# minimumSystem_Hafidin_Alfath.net
KiCad netlist of a schematic drawn in EAGLE
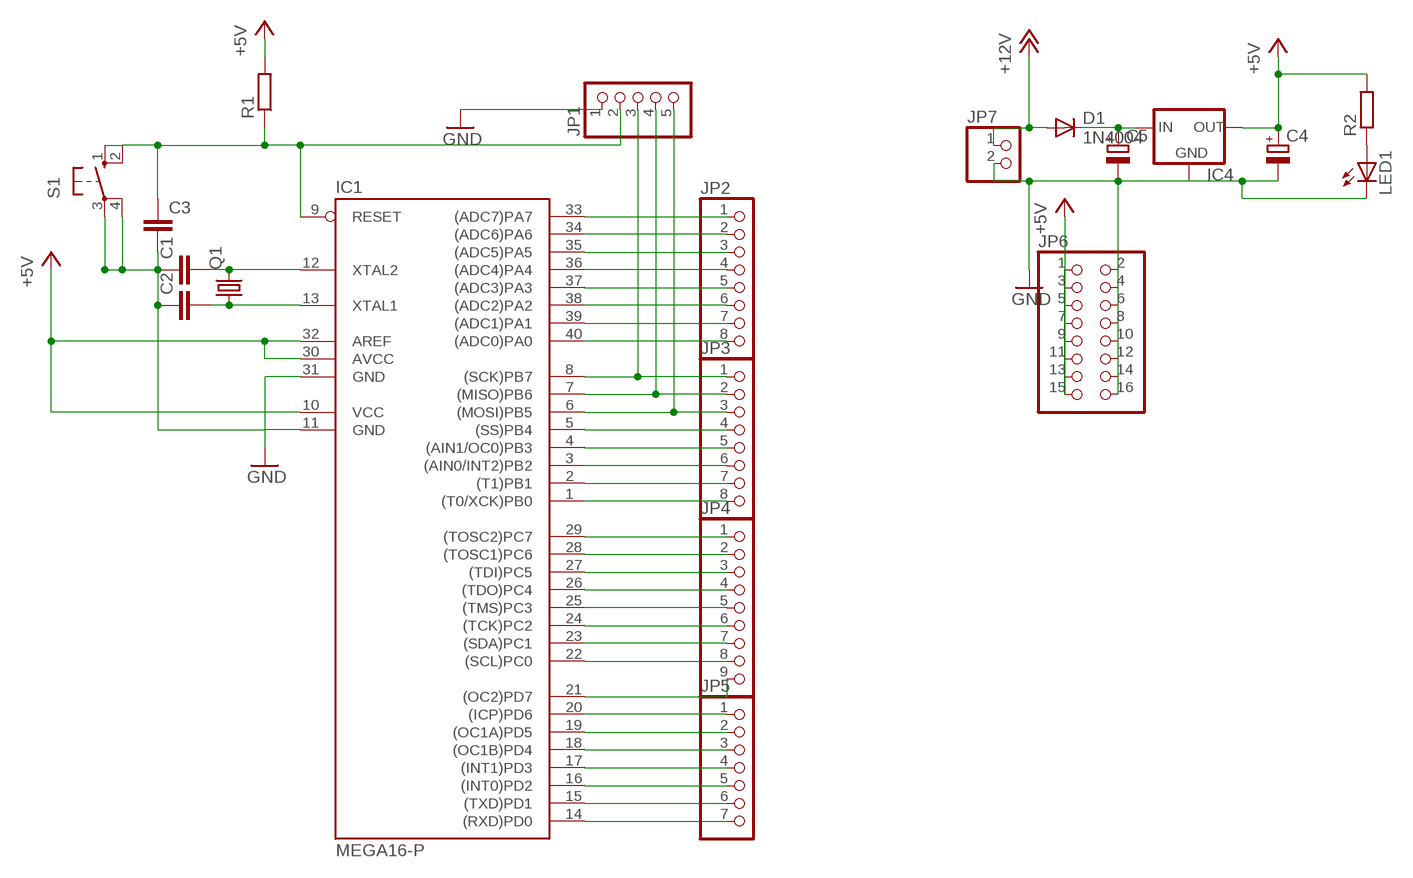
[diagram p0: schematic, sheet 1]

(export (version "E")
  (design (tool "Eeschema 10.0.6"))
  (components
    (comp (ref "C1")
      (value "C-EU025-024X044")
      (footprint "eagle-import:C025-024X044")
      (libsource (lib "eagle-import") (part "C-EU025-024X044"))
    )
    (comp (ref "C2")
      (value "C-EU025-024X044")
      (footprint "eagle-import:C025-024X044")
      (libsource (lib "eagle-import") (part "C-EU025-024X044"))
    )
    (comp (ref "C3")
      (value "C-EU050-025X075")
      (footprint "eagle-import:C050-025X075")
      (libsource (lib "eagle-import") (part "resistor_C-EU050-025X075"))
    )
    (comp (ref "C4")
      (value "CPOL-EUE2.5-5")
      (footprint "eagle-import:E2,5-5")
      (libsource (lib "eagle-import") (part "CPOL-EUE2.5-5"))
    )
    (comp (ref "C5")
      (value "CPOL-EUE2.5-5")
      (footprint "eagle-import:E2,5-5")
      (libsource (lib "eagle-import") (part "CPOL-EUE2.5-5"))
    )
    (comp (ref "D1")
      (value "1N4004")
      (footprint "eagle-import:DO41-10")
      (libsource (lib "eagle-import") (part "1N4004"))
    )
    (comp (ref "IC1")
      (value "MEGA16-P")
      (footprint "eagle-import:DIL40")
      (fields (field (name "MPN") "ATMEGA16-16PU"))
      (libsource (lib "eagle-import") (part "MEGA16-P"))
    )
    (comp (ref "IC4")
      (value "78XXS")
      (footprint "eagle-import:78XXS")
      (libsource (lib "eagle-import") (part "78XXS"))
    )
    (comp (ref "JP1")
      (value "PINHD-1X5")
      (footprint "eagle-import:1X05")
      (libsource (lib "eagle-import") (part "PINHD-1X5"))
    )
    (comp (ref "JP2")
      (value "PINHD-1X8")
      (footprint "eagle-import:1X08")
      (libsource (lib "eagle-import") (part "PINHD-1X8"))
    )
    (comp (ref "JP3")
      (value "PINHD-1X8")
      (footprint "eagle-import:1X08")
      (libsource (lib "eagle-import") (part "PINHD-1X8"))
    )
    (comp (ref "JP4")
      (value "PINHD-1X9")
      (footprint "eagle-import:1X09")
      (libsource (lib "eagle-import") (part "PINHD-1X9"))
    )
    (comp (ref "JP5")
      (value "PINHD-1X7")
      (footprint "eagle-import:1X07")
      (libsource (lib "eagle-import") (part "PINHD-1X7"))
    )
    (comp (ref "JP6")
      (value "PINHD-2X8")
      (footprint "eagle-import:2X08")
      (libsource (lib "eagle-import") (part "PINHD-2X8"))
    )
    (comp (ref "JP7")
      (value "PINHD-1X2")
      (footprint "eagle-import:1X02")
      (libsource (lib "eagle-import") (part "PINHD-1X2"))
    )
    (comp (ref "LED1")
      (value "LED5MM")
      (footprint "eagle-import:LED5MM")
      (libsource (lib "eagle-import") (part "LED5MM"))
    )
    (comp (ref "Q1")
      (value "CRYSTALHC49U-V")
      (footprint "eagle-import:HC49U-V")
      (libsource (lib "eagle-import") (part "CRYSTALHC49U-V"))
    )
    (comp (ref "R1")
      (value "R-EU_0204/7")
      (footprint "eagle-import:0204_7")
      (libsource (lib "eagle-import") (part "R-EU_0204/7"))
    )
    (comp (ref "R2")
      (value "R-EU_0204/7")
      (footprint "eagle-import:0204_7")
      (libsource (lib "eagle-import") (part "R-EU_0204/7"))
    )
    (comp (ref "S1")
      (value "10-XX")
      (footprint "eagle-import:B3F-10XX")
      (fields (field (name "MPN") "B3F-1000"))
      (libsource (lib "eagle-import") (part "10-XX"))
    )
  )
  (nets
    (net (code "1") (name "+5V") (class "Default")
      (node (ref "C4") (pin "+") (pinfunction "+_+") (pintype "passive"))
      (node (ref "IC1") (pin "10") (pinfunction "VCC_10") (pintype "power_in"))
      (node (ref "IC1") (pin "30") (pinfunction "AVCC_30") (pintype "power_in"))
      (node (ref "IC1") (pin "32") (pinfunction "AREF_32") (pintype "passive"))
      (node (ref "IC4") (pin "OUT") (pinfunction "OUT_OUT") (pintype "passive"))
      (node (ref "JP6") (pin "1") (pinfunction "1_1") (pintype "passive"))
      (node (ref "JP6") (pin "11") (pinfunction "11_11") (pintype "passive"))
      (node (ref "JP6") (pin "13") (pinfunction "13_13") (pintype "passive"))
      (node (ref "JP6") (pin "15") (pinfunction "15_15") (pintype "passive"))
      (node (ref "JP6") (pin "3") (pinfunction "3_3") (pintype "passive"))
      (node (ref "JP6") (pin "5") (pinfunction "5_5") (pintype "passive"))
      (node (ref "JP6") (pin "7") (pinfunction "7_7") (pintype "passive"))
      (node (ref "JP6") (pin "9") (pinfunction "9_9") (pintype "passive"))
      (node (ref "R1") (pin "2") (pinfunction "2_2") (pintype "passive"))
      (node (ref "R2") (pin "2") (pinfunction "2_2") (pintype "passive"))
    )
    (net (code "2") (name "+12V") (class "Default")
      (node (ref "D1") (pin "A") (pinfunction "A_A") (pintype "passive"))
      (node (ref "JP7") (pin "1") (pinfunction "1_1") (pintype "passive"))
    )
    (net (code "3") (name "GND") (class "Default")
      (node (ref "C1") (pin "1") (pinfunction "1_1") (pintype "passive"))
      (node (ref "C2") (pin "1") (pinfunction "1_1") (pintype "passive"))
      (node (ref "C3") (pin "2") (pinfunction "2_2") (pintype "passive"))
      (node (ref "C4") (pin "-") (pinfunction "-_-") (pintype "passive"))
      (node (ref "C5") (pin "-") (pinfunction "-_-") (pintype "passive"))
      (node (ref "IC1") (pin "11") (pinfunction "GND_11") (pintype "power_in"))
      (node (ref "IC1") (pin "31") (pinfunction "GND_31") (pintype "power_in"))
      (node (ref "IC4") (pin "GND") (pinfunction "GND_GND") (pintype "input"))
      (node (ref "JP1") (pin "1") (pinfunction "1_1") (pintype "passive"))
      (node (ref "JP6") (pin "10") (pinfunction "10_10") (pintype "passive"))
      (node (ref "JP6") (pin "12") (pinfunction "12_12") (pintype "passive"))
      (node (ref "JP6") (pin "14") (pinfunction "14_14") (pintype "passive"))
      (node (ref "JP6") (pin "16") (pinfunction "16_16") (pintype "passive"))
      (node (ref "JP6") (pin "2") (pinfunction "2_2") (pintype "passive"))
      (node (ref "JP6") (pin "4") (pinfunction "4_4") (pintype "passive"))
      (node (ref "JP6") (pin "6") (pinfunction "6_6") (pintype "passive"))
      (node (ref "JP6") (pin "8") (pinfunction "8_8") (pintype "passive"))
      (node (ref "JP7") (pin "2") (pinfunction "2_2") (pintype "passive"))
      (node (ref "LED1") (pin "K") (pinfunction "C_K") (pintype "passive"))
      (node (ref "S1") (pin "3") (pinfunction "P_3") (pintype "passive"))
      (node (ref "S1") (pin "4") (pinfunction "P1_4") (pintype "passive"))
    )
    (net (code "4") (name "Net-(C5-Pad+)") (class "Default")
      (node (ref "C5") (pin "+") (pinfunction "+_+") (pintype "passive"))
      (node (ref "D1") (pin "C") (pinfunction "C_C") (pintype "passive"))
      (node (ref "IC4") (pin "IN") (pinfunction "IN_IN") (pintype "input"))
    )
    (net (code "5") (name "Net-(IC1-(ADC0)PA0)") (class "Default")
      (node (ref "IC1") (pin "40") (pinfunction "(ADC0)PA0_40") (pintype "bidirectional"))
      (node (ref "JP2") (pin "8") (pinfunction "8_8") (pintype "passive"))
    )
    (net (code "6") (name "Net-(IC1-(ADC1)PA1)") (class "Default")
      (node (ref "IC1") (pin "39") (pinfunction "(ADC1)PA1_39") (pintype "bidirectional"))
      (node (ref "JP2") (pin "7") (pinfunction "7_7") (pintype "passive"))
    )
    (net (code "7") (name "Net-(IC1-(ADC2)PA2)") (class "Default")
      (node (ref "IC1") (pin "38") (pinfunction "(ADC2)PA2_38") (pintype "bidirectional"))
      (node (ref "JP2") (pin "6") (pinfunction "6_6") (pintype "passive"))
    )
    (net (code "8") (name "Net-(IC1-(ADC3)PA3)") (class "Default")
      (node (ref "IC1") (pin "37") (pinfunction "(ADC3)PA3_37") (pintype "bidirectional"))
      (node (ref "JP2") (pin "5") (pinfunction "5_5") (pintype "passive"))
    )
    (net (code "9") (name "Net-(IC1-(ADC4)PA4)") (class "Default")
      (node (ref "IC1") (pin "36") (pinfunction "(ADC4)PA4_36") (pintype "bidirectional"))
      (node (ref "JP2") (pin "4") (pinfunction "4_4") (pintype "passive"))
    )
    (net (code "10") (name "Net-(IC1-(ADC5)PA5)") (class "Default")
      (node (ref "IC1") (pin "35") (pinfunction "(ADC5)PA5_35") (pintype "bidirectional"))
      (node (ref "JP2") (pin "3") (pinfunction "3_3") (pintype "passive"))
    )
    (net (code "11") (name "Net-(IC1-(ADC6)PA6)") (class "Default")
      (node (ref "IC1") (pin "34") (pinfunction "(ADC6)PA6_34") (pintype "bidirectional"))
      (node (ref "JP2") (pin "2") (pinfunction "2_2") (pintype "passive"))
    )
    (net (code "12") (name "Net-(IC1-(ADC7)PA7)") (class "Default")
      (node (ref "IC1") (pin "33") (pinfunction "(ADC7)PA7_33") (pintype "bidirectional"))
      (node (ref "JP2") (pin "1") (pinfunction "1_1") (pintype "passive"))
    )
    (net (code "13") (name "Net-(IC1-(AIN0{slash}INT2)PB2)") (class "Default")
      (node (ref "IC1") (pin "3") (pinfunction "(AIN0/INT2)PB2_3") (pintype "bidirectional"))
      (node (ref "JP3") (pin "6") (pinfunction "6_6") (pintype "passive"))
    )
    (net (code "14") (name "Net-(IC1-(AIN1{slash}OC0)PB3)") (class "Default")
      (node (ref "IC1") (pin "4") (pinfunction "(AIN1/OC0)PB3_4") (pintype "bidirectional"))
      (node (ref "JP3") (pin "5") (pinfunction "5_5") (pintype "passive"))
    )
    (net (code "15") (name "Net-(IC1-(ICP)PD6)") (class "Default")
      (node (ref "IC1") (pin "20") (pinfunction "(ICP)PD6_20") (pintype "bidirectional"))
      (node (ref "JP5") (pin "1") (pinfunction "1_1") (pintype "passive"))
    )
    (net (code "16") (name "Net-(IC1-(INT0)PD2)") (class "Default")
      (node (ref "IC1") (pin "16") (pinfunction "(INT0)PD2_16") (pintype "bidirectional"))
      (node (ref "JP5") (pin "5") (pinfunction "5_5") (pintype "passive"))
    )
    (net (code "17") (name "Net-(IC1-(INT1)PD3)") (class "Default")
      (node (ref "IC1") (pin "17") (pinfunction "(INT1)PD3_17") (pintype "bidirectional"))
      (node (ref "JP5") (pin "4") (pinfunction "4_4") (pintype "passive"))
    )
    (net (code "18") (name "Net-(IC1-(MISO)PB6)") (class "Default")
      (node (ref "IC1") (pin "7") (pinfunction "(MISO)PB6_7") (pintype "bidirectional"))
      (node (ref "JP1") (pin "4") (pinfunction "4_4") (pintype "passive"))
      (node (ref "JP3") (pin "2") (pinfunction "2_2") (pintype "passive"))
    )
    (net (code "19") (name "Net-(IC1-(MOSI)PB5)") (class "Default")
      (node (ref "IC1") (pin "6") (pinfunction "(MOSI)PB5_6") (pintype "bidirectional"))
      (node (ref "JP1") (pin "5") (pinfunction "5_5") (pintype "passive"))
      (node (ref "JP3") (pin "3") (pinfunction "3_3") (pintype "passive"))
    )
    (net (code "20") (name "Net-(IC1-(OC1A)PD5)") (class "Default")
      (node (ref "IC1") (pin "19") (pinfunction "(OC1A)PD5_19") (pintype "bidirectional"))
      (node (ref "JP5") (pin "2") (pinfunction "2_2") (pintype "passive"))
    )
    (net (code "21") (name "Net-(IC1-(OC1B)PD4)") (class "Default")
      (node (ref "IC1") (pin "18") (pinfunction "(OC1B)PD4_18") (pintype "bidirectional"))
      (node (ref "JP5") (pin "3") (pinfunction "3_3") (pintype "passive"))
    )
    (net (code "22") (name "Net-(IC1-(OC2)PD7)") (class "Default")
      (node (ref "IC1") (pin "21") (pinfunction "(OC2)PD7_21") (pintype "bidirectional"))
      (node (ref "JP4") (pin "9") (pinfunction "9_9") (pintype "passive"))
    )
    (net (code "23") (name "Net-(IC1-(RXD)PD0)") (class "Default")
      (node (ref "IC1") (pin "14") (pinfunction "(RXD)PD0_14") (pintype "bidirectional"))
      (node (ref "JP5") (pin "7") (pinfunction "7_7") (pintype "passive"))
    )
    (net (code "24") (name "Net-(IC1-(SCK)PB7)") (class "Default")
      (node (ref "IC1") (pin "8") (pinfunction "(SCK)PB7_8") (pintype "bidirectional"))
      (node (ref "JP1") (pin "3") (pinfunction "3_3") (pintype "passive"))
      (node (ref "JP3") (pin "1") (pinfunction "1_1") (pintype "passive"))
    )
    (net (code "25") (name "Net-(IC1-(SCL)PC0)") (class "Default")
      (node (ref "IC1") (pin "22") (pinfunction "(SCL)PC0_22") (pintype "bidirectional"))
      (node (ref "JP4") (pin "8") (pinfunction "8_8") (pintype "passive"))
    )
    (net (code "26") (name "Net-(IC1-(SDA)PC1)") (class "Default")
      (node (ref "IC1") (pin "23") (pinfunction "(SDA)PC1_23") (pintype "bidirectional"))
      (node (ref "JP4") (pin "7") (pinfunction "7_7") (pintype "passive"))
    )
    (net (code "27") (name "Net-(IC1-(SS)PB4)") (class "Default")
      (node (ref "IC1") (pin "5") (pinfunction "(SS)PB4_5") (pintype "bidirectional"))
      (node (ref "JP3") (pin "4") (pinfunction "4_4") (pintype "passive"))
    )
    (net (code "28") (name "Net-(IC1-(T0{slash}XCK)PB0)") (class "Default")
      (node (ref "IC1") (pin "1") (pinfunction "(T0/XCK)PB0_1") (pintype "bidirectional"))
      (node (ref "JP3") (pin "8") (pinfunction "8_8") (pintype "passive"))
    )
    (net (code "29") (name "Net-(IC1-(T1)PB1)") (class "Default")
      (node (ref "IC1") (pin "2") (pinfunction "(T1)PB1_2") (pintype "bidirectional"))
      (node (ref "JP3") (pin "7") (pinfunction "7_7") (pintype "passive"))
    )
    (net (code "30") (name "Net-(IC1-(TCK)PC2)") (class "Default")
      (node (ref "IC1") (pin "24") (pinfunction "(TCK)PC2_24") (pintype "bidirectional"))
      (node (ref "JP4") (pin "6") (pinfunction "6_6") (pintype "passive"))
    )
    (net (code "31") (name "Net-(IC1-(TDI)PC5)") (class "Default")
      (node (ref "IC1") (pin "27") (pinfunction "(TDI)PC5_27") (pintype "bidirectional"))
      (node (ref "JP4") (pin "3") (pinfunction "3_3") (pintype "passive"))
    )
    (net (code "32") (name "Net-(IC1-(TDO)PC4)") (class "Default")
      (node (ref "IC1") (pin "26") (pinfunction "(TDO)PC4_26") (pintype "bidirectional"))
      (node (ref "JP4") (pin "4") (pinfunction "4_4") (pintype "passive"))
    )
    (net (code "33") (name "Net-(IC1-(TMS)PC3)") (class "Default")
      (node (ref "IC1") (pin "25") (pinfunction "(TMS)PC3_25") (pintype "bidirectional"))
      (node (ref "JP4") (pin "5") (pinfunction "5_5") (pintype "passive"))
    )
    (net (code "34") (name "Net-(IC1-(TOSC1)PC6)") (class "Default")
      (node (ref "IC1") (pin "28") (pinfunction "(TOSC1)PC6_28") (pintype "bidirectional"))
      (node (ref "JP4") (pin "2") (pinfunction "2_2") (pintype "passive"))
    )
    (net (code "35") (name "Net-(IC1-(TOSC2)PC7)") (class "Default")
      (node (ref "IC1") (pin "29") (pinfunction "(TOSC2)PC7_29") (pintype "bidirectional"))
      (node (ref "JP4") (pin "1") (pinfunction "1_1") (pintype "passive"))
    )
    (net (code "36") (name "Net-(IC1-(TXD)PD1)") (class "Default")
      (node (ref "IC1") (pin "15") (pinfunction "(TXD)PD1_15") (pintype "bidirectional"))
      (node (ref "JP5") (pin "6") (pinfunction "6_6") (pintype "passive"))
    )
    (net (code "37") (name "Net-(IC1-RESET)") (class "Default")
      (node (ref "C3") (pin "1") (pinfunction "1_1") (pintype "passive"))
      (node (ref "IC1") (pin "9") (pinfunction "RESET_9") (pintype "input"))
      (node (ref "JP1") (pin "2") (pinfunction "2_2") (pintype "passive"))
      (node (ref "R1") (pin "1") (pinfunction "1_1") (pintype "passive"))
      (node (ref "S1") (pin "1") (pinfunction "S_1") (pintype "passive"))
      (node (ref "S1") (pin "2") (pinfunction "S1_2") (pintype "passive"))
    )
    (net (code "38") (name "Net-(IC1-XTAL1)") (class "Default")
      (node (ref "C2") (pin "2") (pinfunction "2_2") (pintype "passive"))
      (node (ref "IC1") (pin "13") (pinfunction "XTAL1_13") (pintype "bidirectional"))
      (node (ref "Q1") (pin "1") (pinfunction "1_1") (pintype "passive"))
    )
    (net (code "39") (name "Net-(IC1-XTAL2)") (class "Default")
      (node (ref "C1") (pin "2") (pinfunction "2_2") (pintype "passive"))
      (node (ref "IC1") (pin "12") (pinfunction "XTAL2_12") (pintype "bidirectional"))
      (node (ref "Q1") (pin "2") (pinfunction "2_2") (pintype "passive"))
    )
    (net (code "40") (name "Net-(LED1-PadA)") (class "Default")
      (node (ref "LED1") (pin "A") (pinfunction "A_A") (pintype "passive"))
      (node (ref "R2") (pin "1") (pinfunction "1_1") (pintype "passive"))
    )
  )
)
